# UT-61E_MOD.net
KiCad netlist of a schematic drawn in EAGLE
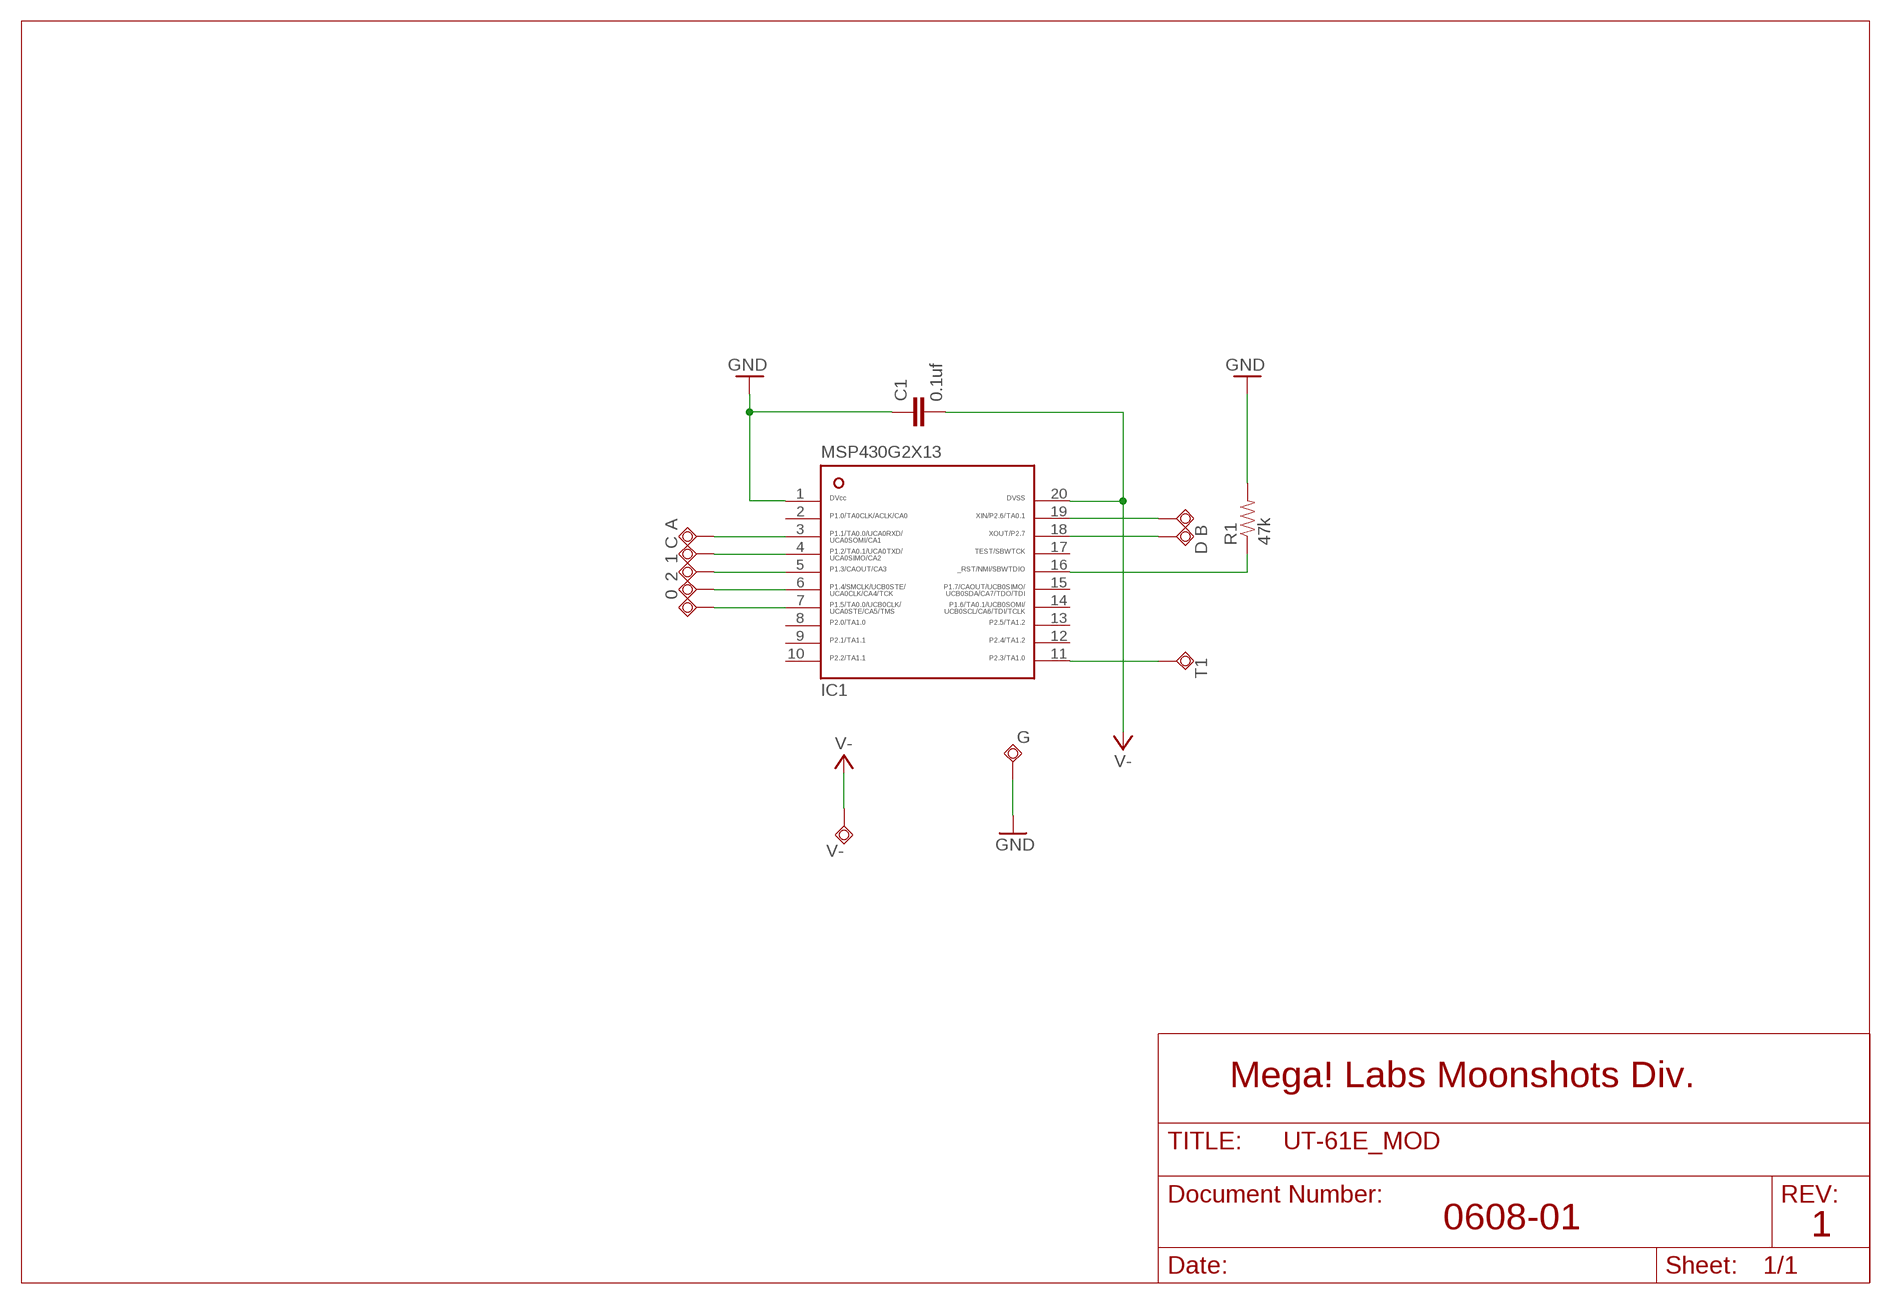
[diagram p0: schematic, sheet 1]

(export (version "E")
  (design (tool "Eeschema 10.0.6"))
  (components
    (comp (ref "0")
      (value "TPSQTP18SQ")
      (footprint "eagle-import:TP18SQ")
      (libsource (lib "eagle-import") (part "TPSQTP18SQ"))
    )
    (comp (ref "1")
      (value "TPSQTP18SQ")
      (footprint "eagle-import:TP18SQ")
      (libsource (lib "eagle-import") (part "TPSQTP18SQ"))
    )
    (comp (ref "2")
      (value "TPSQTP18SQ")
      (footprint "eagle-import:TP18SQ")
      (libsource (lib "eagle-import") (part "TPSQTP18SQ"))
    )
    (comp (ref "A")
      (value "TPSQTP18SQ")
      (footprint "eagle-import:TP18SQ")
      (libsource (lib "eagle-import") (part "TPSQTP18SQ"))
    )
    (comp (ref "B")
      (value "TPSQTP18SQ")
      (footprint "eagle-import:TP18SQ")
      (libsource (lib "eagle-import") (part "TPSQTP18SQ"))
    )
    (comp (ref "C")
      (value "TPSQTP18SQ")
      (footprint "eagle-import:TP18SQ")
      (libsource (lib "eagle-import") (part "TPSQTP18SQ"))
    )
    (comp (ref "C1")
      (value "0.1uf")
      (footprint "eagle-import:0805")
      (libsource (lib "eagle-import") (part "CAP0805"))
    )
    (comp (ref "D")
      (value "TPSQTP18SQ")
      (footprint "eagle-import:TP18SQ")
      (libsource (lib "eagle-import") (part "TPSQTP18SQ"))
    )
    (comp (ref "G")
      (value "TPSQTP18SQ")
      (footprint "eagle-import:TP18SQ")
      (libsource (lib "eagle-import") (part "TPSQTP18SQ"))
    )
    (comp (ref "IC1")
      (value "MSP430G2X13-20PW20")
      (footprint "eagle-import:PW20")
      (libsource (lib "eagle-import") (part "MSP430G2X13-20PW20"))
    )
    (comp (ref "R1")
      (value "47k")
      (footprint "eagle-import:0805")
      (libsource (lib "eagle-import") (part "RESISTOR0805-RES"))
    )
    (comp (ref "T1")
      (value "TPSQTP18SQ")
      (footprint "eagle-import:TP18SQ")
      (libsource (lib "eagle-import") (part "TPSQTP18SQ"))
    )
    (comp (ref "V-")
      (value "TPSQTP18SQ")
      (footprint "eagle-import:TP18SQ")
      (libsource (lib "eagle-import") (part "TPSQTP18SQ"))
    )
  )
  (nets
    (net (code "1") (name "GND") (class "Default")
      (node (ref "C1") (pin "1") (pinfunction "1_1") (pintype "passive"))
      (node (ref "G") (pin "TP") (pinfunction "TP_TP") (pintype "input"))
      (node (ref "IC1") (pin "1") (pinfunction "1_1") (pintype "bidirectional"))
      (node (ref "R1") (pin "2") (pinfunction "2_2") (pintype "passive"))
    )
    (net (code "2") (name "Net-(0-PadTP)") (class "Default")
      (node (ref "0") (pin "TP") (pinfunction "TP_TP") (pintype "input"))
      (node (ref "IC1") (pin "7") (pinfunction "7_7") (pintype "bidirectional"))
    )
    (net (code "3") (name "Net-(1-PadTP)") (class "Default")
      (node (ref "1") (pin "TP") (pinfunction "TP_TP") (pintype "input"))
      (node (ref "IC1") (pin "5") (pinfunction "5_5") (pintype "bidirectional"))
    )
    (net (code "4") (name "Net-(2-PadTP)") (class "Default")
      (node (ref "2") (pin "TP") (pinfunction "TP_TP") (pintype "input"))
      (node (ref "IC1") (pin "6") (pinfunction "6_6") (pintype "bidirectional"))
    )
    (net (code "5") (name "Net-(A-PadTP)") (class "Default")
      (node (ref "A") (pin "TP") (pinfunction "TP_TP") (pintype "input"))
      (node (ref "IC1") (pin "3") (pinfunction "3_3") (pintype "bidirectional"))
    )
    (net (code "6") (name "Net-(B-PadTP)") (class "Default")
      (node (ref "B") (pin "TP") (pinfunction "TP_TP") (pintype "input"))
      (node (ref "IC1") (pin "19") (pinfunction "19_19") (pintype "bidirectional"))
    )
    (net (code "7") (name "Net-(C-PadTP)") (class "Default")
      (node (ref "C") (pin "TP") (pinfunction "TP_TP") (pintype "input"))
      (node (ref "IC1") (pin "4") (pinfunction "4_4") (pintype "bidirectional"))
    )
    (net (code "8") (name "Net-(D-PadTP)") (class "Default")
      (node (ref "D") (pin "TP") (pinfunction "TP_TP") (pintype "input"))
      (node (ref "IC1") (pin "18") (pinfunction "18_18") (pintype "bidirectional"))
    )
    (net (code "9") (name "Net-(IC1-Pad11)") (class "Default")
      (node (ref "IC1") (pin "11") (pinfunction "11_11") (pintype "bidirectional"))
      (node (ref "T1") (pin "TP") (pinfunction "TP_TP") (pintype "input"))
    )
    (net (code "10") (name "Net-(IC1-Pad16)") (class "Default")
      (node (ref "IC1") (pin "16") (pinfunction "16_16") (pintype "bidirectional"))
      (node (ref "R1") (pin "1") (pinfunction "1_1") (pintype "passive"))
    )
    (net (code "11") (name "V-") (class "Default")
      (node (ref "C1") (pin "2") (pinfunction "2_2") (pintype "passive"))
      (node (ref "IC1") (pin "20") (pinfunction "20_20") (pintype "bidirectional"))
      (node (ref "V-") (pin "TP") (pinfunction "TP_TP") (pintype "input"))
    )
    (net (code "12") (name "unconnected-(IC1-Pad2)") (class "Default")
      (node (ref "IC1") (pin "2") (pinfunction "2_2") (pintype "bidirectional"))
    )
    (net (code "13") (name "unconnected-(IC1-Pad8)") (class "Default")
      (node (ref "IC1") (pin "8") (pinfunction "8_8") (pintype "bidirectional"))
    )
    (net (code "14") (name "unconnected-(IC1-Pad9)") (class "Default")
      (node (ref "IC1") (pin "9") (pinfunction "9_9") (pintype "bidirectional"))
    )
    (net (code "15") (name "unconnected-(IC1-Pad10)") (class "Default")
      (node (ref "IC1") (pin "10") (pinfunction "10_10") (pintype "bidirectional"))
    )
    (net (code "16") (name "unconnected-(IC1-Pad12)") (class "Default")
      (node (ref "IC1") (pin "12") (pinfunction "12_12") (pintype "bidirectional"))
    )
    (net (code "17") (name "unconnected-(IC1-Pad13)") (class "Default")
      (node (ref "IC1") (pin "13") (pinfunction "13_13") (pintype "bidirectional"))
    )
    (net (code "18") (name "unconnected-(IC1-Pad14)") (class "Default")
      (node (ref "IC1") (pin "14") (pinfunction "14_14") (pintype "bidirectional"))
    )
    (net (code "19") (name "unconnected-(IC1-Pad15)") (class "Default")
      (node (ref "IC1") (pin "15") (pinfunction "15_15") (pintype "bidirectional"))
    )
    (net (code "20") (name "unconnected-(IC1-Pad17)") (class "Default")
      (node (ref "IC1") (pin "17") (pinfunction "17_17") (pintype "bidirectional"))
    )
  )
)
